# Serial_devises.net
KiCad netlist of a schematic drawn in Altium Designer
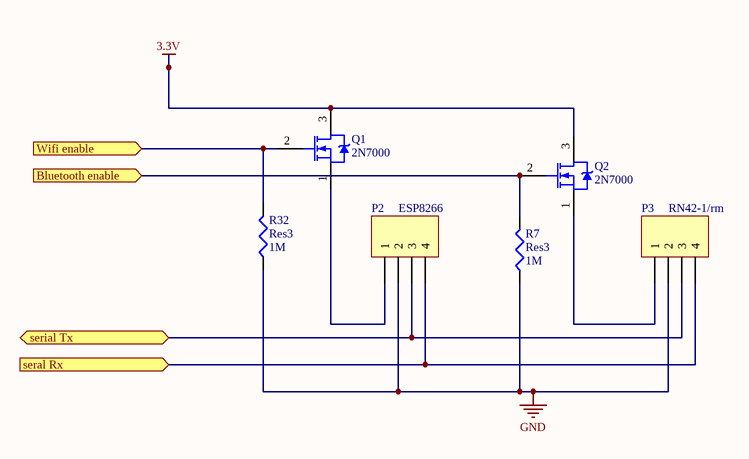
[diagram p0: Serial devises.SchDoc]

(export (version "E")
  (design (tool "Eeschema 10.0.6"))
  (components
    (comp (ref "P2")
      (value "ESP8266")
      (footprint "HDR1X4")
      (description "Header, 4-Pin")
      (fields (field (name "PUBLISHER") "Altium Limited"))
      (libsource (lib "Miscellaneous Connectors") (part "Header 4"))
    )
    (comp (ref "P3")
      (value "RN42-1/rm")
      (footprint "HDR1X4")
      (description "Header, 4-Pin")
      (fields (field (name "PUBLISHER") "Altium Limited"))
      (libsource (lib "Miscellaneous Connectors") (part "Header 4"))
    )
    (comp (ref "Q1")
      (value "2N7000")
      (footprint "ONSC-SOT-323-3-419-04_V")
      (description "Small Signal MOSFET, 200 mA, 60 V, N-Channel, 3-Pin TO-92, Bulk Box")
      (fields (field (name "MANUFACTURER") "On Semiconductor"))
      (libsource (lib "ON Semi MOSFETs") (part "2N7000"))
    )
    (comp (ref "Q2")
      (value "2N7000")
      (footprint "ONSC-SOT-323-3-419-04_V")
      (description "Small Signal MOSFET, 200 mA, 60 V, N-Channel, 3-Pin TO-92, Bulk Box")
      (fields (field (name "MANUFACTURER") "On Semiconductor"))
      (libsource (lib "ON Semi MOSFETs") (part "2N7000"))
    )
    (comp (ref "R7")
      (value "Res3")
      (footprint "0402")
      (description "Resistor")
      (fields (field (name "ALTIUM_VALUE") "1M") (field (name "PUBLISHER") "Altium Limited"))
      (libsource (lib "Miscellaneous Devices") (part "Res3"))
    )
    (comp (ref "R32")
      (value "Res3")
      (footprint "0402")
      (description "Resistor")
      (fields (field (name "ALTIUM_VALUE") "1M") (field (name "PUBLISHER") "Altium Limited"))
      (libsource (lib "Miscellaneous Devices") (part "Res3"))
    )
  )
  (nets
    (net (code "1") (name "/Bluetooth enable") (class "Default")
      (node (ref "Q2") (pin "2") (pinfunction "G_2") (pintype "passive"))
      (node (ref "R7") (pin "2") (pinfunction "2_2") (pintype "passive"))
    )
    (net (code "2") (name "/Wifi enable") (class "Default")
      (node (ref "Q1") (pin "2") (pinfunction "G_2") (pintype "passive"))
      (node (ref "R32") (pin "2") (pinfunction "2_2") (pintype "passive"))
    )
    (net (code "3") (name "/seral Rx") (class "Default")
      (node (ref "P2") (pin "4") (pinfunction "4_4") (pintype "passive"))
      (node (ref "P3") (pin "4") (pinfunction "4_4") (pintype "passive"))
    )
    (net (code "4") (name "/serial Tx") (class "Default")
      (node (ref "P2") (pin "3") (pinfunction "3_3") (pintype "passive"))
      (node (ref "P3") (pin "3") (pinfunction "3_3") (pintype "passive"))
    )
    (net (code "5") (name "3.3V") (class "Default")
      (node (ref "Q1") (pin "3") (pinfunction "D_3") (pintype "passive"))
      (node (ref "Q2") (pin "3") (pinfunction "D_3") (pintype "passive"))
    )
    (net (code "6") (name "GND") (class "Default")
      (node (ref "P2") (pin "2") (pinfunction "2_2") (pintype "passive"))
      (node (ref "P3") (pin "2") (pinfunction "2_2") (pintype "passive"))
      (node (ref "R32") (pin "1") (pinfunction "1_1") (pintype "passive"))
      (node (ref "R7") (pin "1") (pinfunction "1_1") (pintype "passive"))
    )
    (net (code "7") (name "Net-(Q1-S)") (class "Default")
      (node (ref "P2") (pin "1") (pinfunction "1_1") (pintype "passive"))
      (node (ref "Q1") (pin "1") (pinfunction "S_1") (pintype "passive"))
    )
    (net (code "8") (name "Net-(Q2-S)") (class "Default")
      (node (ref "P3") (pin "1") (pinfunction "1_1") (pintype "passive"))
      (node (ref "Q2") (pin "1") (pinfunction "S_1") (pintype "passive"))
    )
  )
)
